# PCBTASK_2021-05-22.net
KiCad netlist of a schematic drawn in EasyEDA
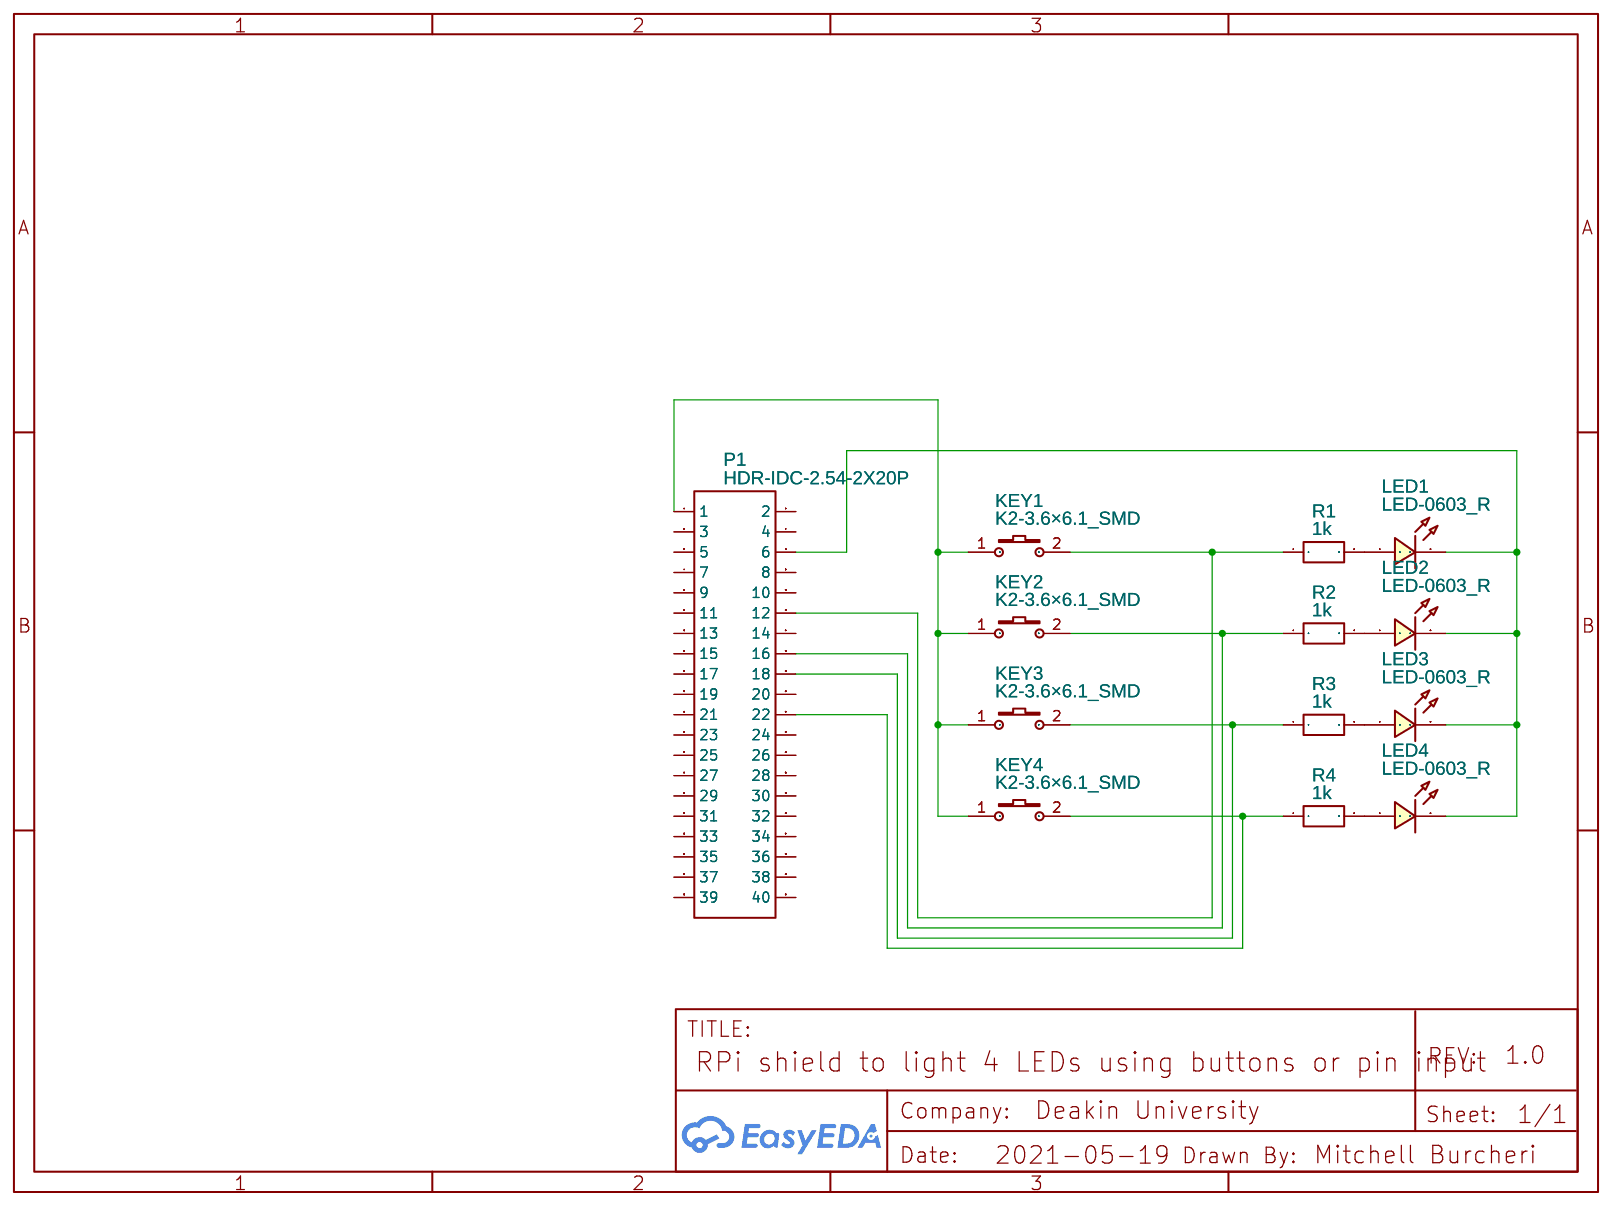
[diagram p0: schematic sheet]

(export (version "E")
  (design (tool "Eeschema 10.0.6"))
  (components
    (comp (ref "KEY1")
      (value "K2-3.6×6.1_SMD")
      (fields
        (field (name "BOM_Manufacturer Part") "K2-1107ST-A4SW-06")
        (field (name "BOM_Supplier Part") "C118141")
      )
      (libsource (lib "") (part "K2-3.6×6.1_SMD"))
    )
    (comp (ref "KEY2")
      (value "K2-3.6×6.1_SMD")
      (fields
        (field (name "BOM_Manufacturer Part") "K2-1107ST-A4SW-06")
        (field (name "BOM_Supplier Part") "C118141")
      )
      (libsource (lib "") (part "K2-3.6×6.1_SMD"))
    )
    (comp (ref "KEY3")
      (value "K2-3.6×6.1_SMD")
      (fields
        (field (name "BOM_Manufacturer Part") "K2-1107ST-A4SW-06")
        (field (name "BOM_Supplier Part") "C118141")
      )
      (libsource (lib "") (part "K2-3.6×6.1_SMD"))
    )
    (comp (ref "KEY4")
      (value "K2-3.6×6.1_SMD")
      (fields
        (field (name "BOM_Manufacturer Part") "K2-1107ST-A4SW-06")
        (field (name "BOM_Supplier Part") "C118141")
      )
      (libsource (lib "") (part "K2-3.6×6.1_SMD"))
    )
    (comp (ref "LED1")
      (value "LED-0603_R")
      (fields
        (field (name "BOM_Manufacturer Part") "19-217/R6C-AL1M2VY/3T")
        (field (name "BOM_Supplier Part") "C72044")
      )
      (libsource (lib "") (part "LED-0603_R"))
    )
    (comp (ref "LED2")
      (value "LED-0603_R")
      (fields
        (field (name "BOM_Manufacturer Part") "19-217/R6C-AL1M2VY/3T")
        (field (name "BOM_Supplier Part") "C72044")
      )
      (libsource (lib "") (part "LED-0603_R"))
    )
    (comp (ref "LED3")
      (value "LED-0603_R")
      (fields
        (field (name "BOM_Manufacturer Part") "19-217/R6C-AL1M2VY/3T")
        (field (name "BOM_Supplier Part") "C72044")
      )
      (libsource (lib "") (part "LED-0603_R"))
    )
    (comp (ref "LED4")
      (value "LED-0603_R")
      (fields
        (field (name "BOM_Manufacturer Part") "19-217/R6C-AL1M2VY/3T")
        (field (name "BOM_Supplier Part") "C72044")
      )
      (libsource (lib "") (part "LED-0603_R"))
    )
    (comp (ref "P1")
      (value "HDR-IDC-2.54-2X20P")
      (fields
        (field (name "BOM_Manufacturer Part") "IDC Box 2X20 2.54MM")
        (field (name "BOM_Supplier Part") "C9138")
      )
      (libsource (lib "") (part "HDR-IDC-2.54-2X20P"))
    )
    (comp (ref "R1") (value "1k") (libsource (lib "") (part "R_0201_EU")))
    (comp (ref "R2") (value "1k") (libsource (lib "") (part "R_0201_EU")))
    (comp (ref "R3") (value "1k") (libsource (lib "") (part "R_0201_EU")))
    (comp (ref "R4") (value "1k") (libsource (lib "") (part "R_0201_EU")))
  )
  (nets
    (net (code "1") (name "Net-(KEY1-Pad1)") (class "Default")
      (node (ref "KEY1") (pin "1") (pinfunction "1_1") (pintype "unspecified"))
      (node (ref "KEY2") (pin "1") (pinfunction "1_1") (pintype "unspecified"))
      (node (ref "KEY3") (pin "1") (pinfunction "1_1") (pintype "unspecified"))
      (node (ref "KEY4") (pin "1") (pinfunction "1_1") (pintype "unspecified"))
      (node (ref "P1") (pin "1") (pinfunction "1_1") (pintype "unspecified"))
    )
    (net (code "2") (name "Net-(KEY1-Pad2)") (class "Default")
      (node (ref "KEY1") (pin "2") (pinfunction "2_2") (pintype "unspecified"))
      (node (ref "P1") (pin "12") (pinfunction "12_12") (pintype "unspecified"))
      (node (ref "R1") (pin "1") (pinfunction "1_1") (pintype "unspecified"))
    )
    (net (code "3") (name "Net-(KEY2-Pad2)") (class "Default")
      (node (ref "KEY2") (pin "2") (pinfunction "2_2") (pintype "unspecified"))
      (node (ref "P1") (pin "16") (pinfunction "16_16") (pintype "unspecified"))
      (node (ref "R2") (pin "1") (pinfunction "1_1") (pintype "unspecified"))
    )
    (net (code "4") (name "Net-(KEY3-Pad2)") (class "Default")
      (node (ref "KEY3") (pin "2") (pinfunction "2_2") (pintype "unspecified"))
      (node (ref "P1") (pin "18") (pinfunction "18_18") (pintype "unspecified"))
      (node (ref "R3") (pin "1") (pinfunction "1_1") (pintype "unspecified"))
    )
    (net (code "5") (name "Net-(KEY4-Pad2)") (class "Default")
      (node (ref "KEY4") (pin "2") (pinfunction "2_2") (pintype "unspecified"))
      (node (ref "P1") (pin "22") (pinfunction "22_22") (pintype "unspecified"))
      (node (ref "R4") (pin "1") (pinfunction "1_1") (pintype "unspecified"))
    )
    (net (code "6") (name "Net-(LED1-Pad1)") (class "Default")
      (node (ref "LED1") (pin "1") (pinfunction "1_1") (pintype "unspecified"))
      (node (ref "R1") (pin "2") (pinfunction "2_2") (pintype "unspecified"))
    )
    (net (code "7") (name "Net-(LED1-Pad2)") (class "Default")
      (node (ref "LED1") (pin "2") (pinfunction "2_2") (pintype "unspecified"))
      (node (ref "LED2") (pin "2") (pinfunction "2_2") (pintype "unspecified"))
      (node (ref "LED3") (pin "2") (pinfunction "2_2") (pintype "unspecified"))
      (node (ref "LED4") (pin "2") (pinfunction "2_2") (pintype "unspecified"))
      (node (ref "P1") (pin "6") (pinfunction "6_6") (pintype "unspecified"))
    )
    (net (code "8") (name "Net-(LED2-Pad1)") (class "Default")
      (node (ref "LED2") (pin "1") (pinfunction "1_1") (pintype "unspecified"))
      (node (ref "R2") (pin "2") (pinfunction "2_2") (pintype "unspecified"))
    )
    (net (code "9") (name "Net-(LED3-Pad1)") (class "Default")
      (node (ref "LED3") (pin "1") (pinfunction "1_1") (pintype "unspecified"))
      (node (ref "R3") (pin "2") (pinfunction "2_2") (pintype "unspecified"))
    )
    (net (code "10") (name "Net-(LED4-Pad1)") (class "Default")
      (node (ref "LED4") (pin "1") (pinfunction "1_1") (pintype "unspecified"))
      (node (ref "R4") (pin "2") (pinfunction "2_2") (pintype "unspecified"))
    )
    (net (code "11") (name "unconnected-(P1-Pad2)") (class "Default")
      (node (ref "P1") (pin "2") (pinfunction "2_2") (pintype "unspecified"))
    )
    (net (code "12") (name "unconnected-(P1-Pad3)") (class "Default")
      (node (ref "P1") (pin "3") (pinfunction "3_3") (pintype "unspecified"))
    )
    (net (code "13") (name "unconnected-(P1-Pad4)") (class "Default")
      (node (ref "P1") (pin "4") (pinfunction "4_4") (pintype "unspecified"))
    )
    (net (code "14") (name "unconnected-(P1-Pad5)") (class "Default")
      (node (ref "P1") (pin "5") (pinfunction "5_5") (pintype "unspecified"))
    )
    (net (code "15") (name "unconnected-(P1-Pad7)") (class "Default")
      (node (ref "P1") (pin "7") (pinfunction "7_7") (pintype "unspecified"))
    )
    (net (code "16") (name "unconnected-(P1-Pad8)") (class "Default")
      (node (ref "P1") (pin "8") (pinfunction "8_8") (pintype "unspecified"))
    )
    (net (code "17") (name "unconnected-(P1-Pad9)") (class "Default")
      (node (ref "P1") (pin "9") (pinfunction "9_9") (pintype "unspecified"))
    )
    (net (code "18") (name "unconnected-(P1-Pad10)") (class "Default")
      (node (ref "P1") (pin "10") (pinfunction "10_10") (pintype "unspecified"))
    )
    (net (code "19") (name "unconnected-(P1-Pad11)") (class "Default")
      (node (ref "P1") (pin "11") (pinfunction "11_11") (pintype "unspecified"))
    )
    (net (code "20") (name "unconnected-(P1-Pad13)") (class "Default")
      (node (ref "P1") (pin "13") (pinfunction "13_13") (pintype "unspecified"))
    )
    (net (code "21") (name "unconnected-(P1-Pad14)") (class "Default")
      (node (ref "P1") (pin "14") (pinfunction "14_14") (pintype "unspecified"))
    )
    (net (code "22") (name "unconnected-(P1-Pad15)") (class "Default")
      (node (ref "P1") (pin "15") (pinfunction "15_15") (pintype "unspecified"))
    )
    (net (code "23") (name "unconnected-(P1-Pad17)") (class "Default")
      (node (ref "P1") (pin "17") (pinfunction "17_17") (pintype "unspecified"))
    )
    (net (code "24") (name "unconnected-(P1-Pad19)") (class "Default")
      (node (ref "P1") (pin "19") (pinfunction "19_19") (pintype "unspecified"))
    )
    (net (code "25") (name "unconnected-(P1-Pad20)") (class "Default")
      (node (ref "P1") (pin "20") (pinfunction "20_20") (pintype "unspecified"))
    )
    (net (code "26") (name "unconnected-(P1-Pad21)") (class "Default")
      (node (ref "P1") (pin "21") (pinfunction "21_21") (pintype "unspecified"))
    )
    (net (code "27") (name "unconnected-(P1-Pad23)") (class "Default")
      (node (ref "P1") (pin "23") (pinfunction "23_23") (pintype "unspecified"))
    )
    (net (code "28") (name "unconnected-(P1-Pad24)") (class "Default")
      (node (ref "P1") (pin "24") (pinfunction "24_24") (pintype "unspecified"))
    )
    (net (code "29") (name "unconnected-(P1-Pad25)") (class "Default")
      (node (ref "P1") (pin "25") (pinfunction "25_25") (pintype "unspecified"))
    )
    (net (code "30") (name "unconnected-(P1-Pad26)") (class "Default")
      (node (ref "P1") (pin "26") (pinfunction "26_26") (pintype "unspecified"))
    )
    (net (code "31") (name "unconnected-(P1-Pad27)") (class "Default")
      (node (ref "P1") (pin "27") (pinfunction "27_27") (pintype "unspecified"))
    )
    (net (code "32") (name "unconnected-(P1-Pad28)") (class "Default")
      (node (ref "P1") (pin "28") (pinfunction "28_28") (pintype "unspecified"))
    )
    (net (code "33") (name "unconnected-(P1-Pad29)") (class "Default")
      (node (ref "P1") (pin "29") (pinfunction "29_29") (pintype "unspecified"))
    )
    (net (code "34") (name "unconnected-(P1-Pad30)") (class "Default")
      (node (ref "P1") (pin "30") (pinfunction "30_30") (pintype "unspecified"))
    )
    (net (code "35") (name "unconnected-(P1-Pad31)") (class "Default")
      (node (ref "P1") (pin "31") (pinfunction "31_31") (pintype "unspecified"))
    )
    (net (code "36") (name "unconnected-(P1-Pad32)") (class "Default")
      (node (ref "P1") (pin "32") (pinfunction "32_32") (pintype "unspecified"))
    )
    (net (code "37") (name "unconnected-(P1-Pad33)") (class "Default")
      (node (ref "P1") (pin "33") (pinfunction "33_33") (pintype "unspecified"))
    )
    (net (code "38") (name "unconnected-(P1-Pad34)") (class "Default")
      (node (ref "P1") (pin "34") (pinfunction "34_34") (pintype "unspecified"))
    )
    (net (code "39") (name "unconnected-(P1-Pad35)") (class "Default")
      (node (ref "P1") (pin "35") (pinfunction "35_35") (pintype "unspecified"))
    )
    (net (code "40") (name "unconnected-(P1-Pad36)") (class "Default")
      (node (ref "P1") (pin "36") (pinfunction "36_36") (pintype "unspecified"))
    )
    (net (code "41") (name "unconnected-(P1-Pad37)") (class "Default")
      (node (ref "P1") (pin "37") (pinfunction "37_37") (pintype "unspecified"))
    )
    (net (code "42") (name "unconnected-(P1-Pad38)") (class "Default")
      (node (ref "P1") (pin "38") (pinfunction "38_38") (pintype "unspecified"))
    )
    (net (code "43") (name "unconnected-(P1-Pad39)") (class "Default")
      (node (ref "P1") (pin "39") (pinfunction "39_39") (pintype "unspecified"))
    )
    (net (code "44") (name "unconnected-(P1-Pad40)") (class "Default")
      (node (ref "P1") (pin "40") (pinfunction "40_40") (pintype "unspecified"))
    )
  )
)
